# Controller-Modul.net
KiCad netlist of a schematic drawn in EAGLE
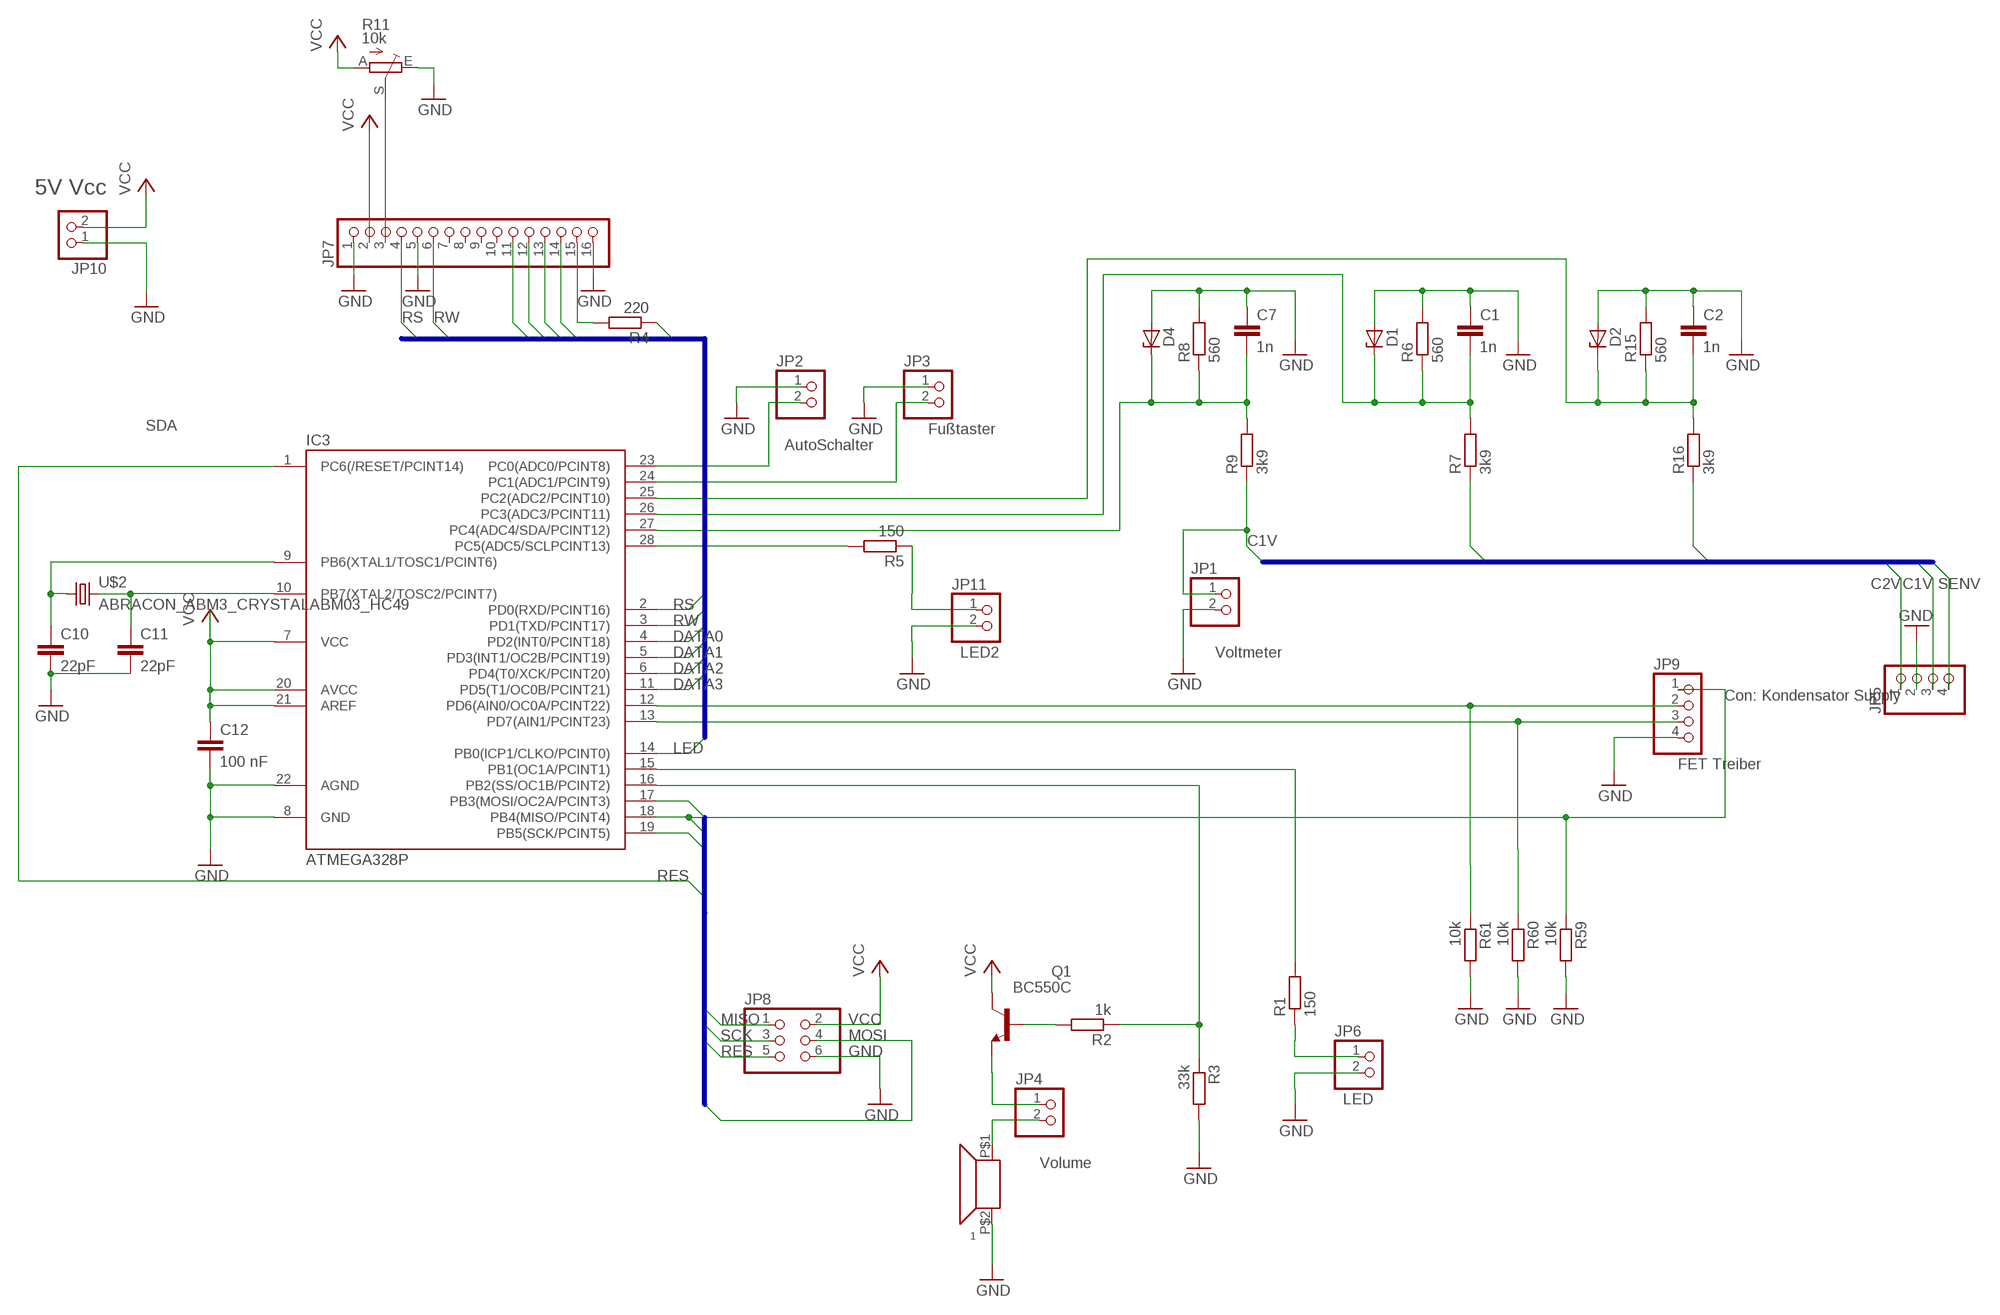
[diagram p0: schematic, sheet 1]

(export (version "E")
  (design (tool "Eeschema 10.0.6"))
  (components
    (comp (ref "1")
      (value "SUMMER4")
      (footprint "eagle-import:PIEZO-INDIKATOR-KPMG")
      (libsource (lib "eagle-import") (part "SUMMER4"))
    )
    (comp (ref "C1")
      (value "1n")
      (footprint "eagle-import:C0603K")
      (libsource (lib "eagle-import") (part "C-EUC0603K"))
    )
    (comp (ref "C2")
      (value "1n")
      (footprint "eagle-import:C0603K")
      (libsource (lib "eagle-import") (part "C-EUC0603K"))
    )
    (comp (ref "C7")
      (value "1n")
      (footprint "eagle-import:C0603K")
      (libsource (lib "eagle-import") (part "C-EUC0603K"))
    )
    (comp (ref "C10")
      (value "22pF")
      (footprint "eagle-import:C0603K")
      (libsource (lib "eagle-import") (part "resistor_C-EUC0603K"))
    )
    (comp (ref "C11")
      (value "22pF")
      (footprint "eagle-import:C0603K")
      (libsource (lib "eagle-import") (part "resistor_C-EUC0603K"))
    )
    (comp (ref "C12")
      (value "100 nF")
      (footprint "eagle-import:C0603")
      (libsource (lib "eagle-import") (part "resistor_C-EUC0603"))
    )
    (comp (ref "D1")
      (value "ZENER-DIODESOT23")
      (footprint "eagle-import:SOT23")
      (libsource (lib "eagle-import") (part "ZENER-DIODESOT23"))
    )
    (comp (ref "D2")
      (value "ZENER-DIODESOT23")
      (footprint "eagle-import:SOT23")
      (libsource (lib "eagle-import") (part "ZENER-DIODESOT23"))
    )
    (comp (ref "D4")
      (value "ZENER-DIODESOT23")
      (footprint "eagle-import:SOT23")
      (libsource (lib "eagle-import") (part "ZENER-DIODESOT23"))
    )
    (comp (ref "IC3")
      (value "ATMEGA328P")
      (footprint "eagle-import:DIL28-3")
      (libsource (lib "eagle-import") (part "MEGA48/88/168-PU"))
    )
    (comp (ref "JP1")
      (value "PINHD-1X2")
      (footprint "eagle-import:1X02")
      (libsource (lib "eagle-import") (part "PINHD-1X2"))
    )
    (comp (ref "JP2")
      (value "PINHD-1X2")
      (footprint "eagle-import:1X02")
      (libsource (lib "eagle-import") (part "PINHD-1X2"))
    )
    (comp (ref "JP3")
      (value "PINHD-1X2")
      (footprint "eagle-import:1X02")
      (libsource (lib "eagle-import") (part "PINHD-1X2"))
    )
    (comp (ref "JP4")
      (value "PINHD-1X2")
      (footprint "eagle-import:1X02")
      (libsource (lib "eagle-import") (part "PINHD-1X2"))
    )
    (comp (ref "JP5")
      (value "PINHD-1X4")
      (footprint "eagle-import:1X04")
      (libsource (lib "eagle-import") (part "PINHD-1X4"))
    )
    (comp (ref "JP6")
      (value "PINHD-1X2")
      (footprint "eagle-import:1X02")
      (libsource (lib "eagle-import") (part "PINHD-1X2"))
    )
    (comp (ref "JP7")
      (value "PINHD-1X16")
      (footprint "eagle-import:1X16")
      (libsource (lib "eagle-import") (part "PINHD-1X16"))
    )
    (comp (ref "JP8")
      (value "PINHD-2X3")
      (footprint "eagle-import:2X03")
      (libsource (lib "eagle-import") (part "PINHD-2X3"))
    )
    (comp (ref "JP9")
      (value "PINHD-1X4")
      (footprint "eagle-import:1X04")
      (libsource (lib "eagle-import") (part "PINHD-1X4"))
    )
    (comp (ref "JP10")
      (value "PINHD-1X2")
      (footprint "eagle-import:1X02")
      (libsource (lib "eagle-import") (part "PINHD-1X2"))
    )
    (comp (ref "JP11")
      (value "PINHD-1X2")
      (footprint "eagle-import:1X02")
      (libsource (lib "eagle-import") (part "PINHD-1X2"))
    )
    (comp (ref "Q1")
      (value "BC550C")
      (footprint "eagle-import:TO92-EBC")
      (libsource (lib "eagle-import") (part "BC550C"))
    )
    (comp (ref "R1")
      (value "150")
      (footprint "eagle-import:R1206")
      (libsource (lib "eagle-import") (part "R-EU_R1206"))
    )
    (comp (ref "R2")
      (value "1k")
      (footprint "eagle-import:R1206")
      (libsource (lib "eagle-import") (part "resistor_R-EU_R1206"))
    )
    (comp (ref "R3")
      (value "33k")
      (footprint "eagle-import:R1206")
      (libsource (lib "eagle-import") (part "resistor_R-EU_R1206"))
    )
    (comp (ref "R4")
      (value "220")
      (footprint "eagle-import:R1206")
      (libsource (lib "eagle-import") (part "resistor_R-EU_R1206"))
    )
    (comp (ref "R5")
      (value "150")
      (footprint "eagle-import:R1206")
      (libsource (lib "eagle-import") (part "R-EU_R1206"))
    )
    (comp (ref "R6")
      (value "560")
      (footprint "eagle-import:R1206")
      (libsource (lib "eagle-import") (part "resistor_R-EU_R1206"))
    )
    (comp (ref "R7")
      (value "3k9")
      (footprint "eagle-import:R1206")
      (libsource (lib "eagle-import") (part "resistor_R-EU_R1206"))
    )
    (comp (ref "R8")
      (value "560")
      (footprint "eagle-import:R1206")
      (libsource (lib "eagle-import") (part "resistor_R-EU_R1206"))
    )
    (comp (ref "R9")
      (value "3k9")
      (footprint "eagle-import:R1206")
      (libsource (lib "eagle-import") (part "resistor_R-EU_R1206"))
    )
    (comp (ref "R11")
      (value "10k")
      (footprint "eagle-import:PT-10")
      (libsource (lib "eagle-import") (part "TRIM_EU-PT10"))
    )
    (comp (ref "R15")
      (value "560")
      (footprint "eagle-import:R1206")
      (libsource (lib "eagle-import") (part "resistor_R-EU_R1206"))
    )
    (comp (ref "R16")
      (value "3k9")
      (footprint "eagle-import:R1206")
      (libsource (lib "eagle-import") (part "resistor_R-EU_R1206"))
    )
    (comp (ref "R59")
      (value "10k")
      (footprint "eagle-import:R1206")
      (libsource (lib "eagle-import") (part "resistor_R-EU_R1206"))
    )
    (comp (ref "R60")
      (value "10k")
      (footprint "eagle-import:R1206")
      (libsource (lib "eagle-import") (part "resistor_R-EU_R1206"))
    )
    (comp (ref "R61")
      (value "10k")
      (footprint "eagle-import:R1206")
      (libsource (lib "eagle-import") (part "resistor_R-EU_R1206"))
    )
    (comp (ref "U$2")
      (value "ABRACON_ABM3_CRYSTALABM03_HC49")
      (footprint "eagle-import:ABM03_HC49")
      (libsource (lib "eagle-import") (part "ABRACON_ABM3_CRYSTALABM03_HC49"))
    )
  )
  (nets
    (net (code "1") (name "/C1V") (class "Default")
      (node (ref "JP1") (pin "1") (pinfunction "1_1") (pintype "passive"))
      (node (ref "JP5") (pin "3") (pinfunction "3_3") (pintype "passive"))
      (node (ref "R9") (pin "1") (pinfunction "1_1") (pintype "passive"))
    )
    (net (code "2") (name "/C2V") (class "Default")
      (node (ref "JP5") (pin "1") (pinfunction "1_1") (pintype "passive"))
      (node (ref "R7") (pin "1") (pinfunction "1_1") (pintype "passive"))
    )
    (net (code "3") (name "/DATA0") (class "Default")
      (node (ref "IC3") (pin "4") (pinfunction "PD2(INT0/PCINT18)_4") (pintype "bidirectional"))
      (node (ref "JP7") (pin "11") (pinfunction "11_11") (pintype "passive"))
    )
    (net (code "4") (name "/DATA1") (class "Default")
      (node (ref "IC3") (pin "5") (pinfunction "PD3(INT1/OC2B/PCINT19)_5") (pintype "bidirectional"))
      (node (ref "JP7") (pin "12") (pinfunction "12_12") (pintype "passive"))
    )
    (net (code "5") (name "/DATA2") (class "Default")
      (node (ref "IC3") (pin "6") (pinfunction "PD4(T0/XCK/PCINT20)_6") (pintype "bidirectional"))
      (node (ref "JP7") (pin "13") (pinfunction "13_13") (pintype "passive"))
    )
    (net (code "6") (name "/DATA3") (class "Default")
      (node (ref "IC3") (pin "11") (pinfunction "PD5(T1/OC0B/PCINT21)_11") (pintype "bidirectional"))
      (node (ref "JP7") (pin "14") (pinfunction "14_14") (pintype "passive"))
    )
    (net (code "7") (name "/LED") (class "Default")
      (node (ref "IC3") (pin "14") (pinfunction "PB0(ICP1/CLKO/PCINT0)_14") (pintype "bidirectional"))
      (node (ref "R4") (pin "1") (pinfunction "1_1") (pintype "passive"))
    )
    (net (code "8") (name "/MISO") (class "Default")
      (node (ref "IC3") (pin "18") (pinfunction "PB4(MISO/PCINT4)_18") (pintype "bidirectional"))
      (node (ref "JP8") (pin "1") (pinfunction "1_1") (pintype "passive"))
      (node (ref "JP9") (pin "1") (pinfunction "1_1") (pintype "passive"))
      (node (ref "R59") (pin "1") (pinfunction "1_1") (pintype "passive"))
    )
    (net (code "9") (name "/MOSI") (class "Default")
      (node (ref "IC3") (pin "17") (pinfunction "PB3(MOSI/OC2A/PCINT3)_17") (pintype "bidirectional"))
      (node (ref "JP8") (pin "4") (pinfunction "4_4") (pintype "passive"))
    )
    (net (code "10") (name "/RES") (class "Default")
      (node (ref "IC3") (pin "1") (pinfunction "PC6(/RESET/PCINT14)_1") (pintype "bidirectional"))
      (node (ref "JP8") (pin "5") (pinfunction "5_5") (pintype "passive"))
    )
    (net (code "11") (name "/RS") (class "Default")
      (node (ref "IC3") (pin "2") (pinfunction "PD0(RXD/PCINT16)_2") (pintype "bidirectional"))
      (node (ref "JP7") (pin "4") (pinfunction "4_4") (pintype "passive"))
    )
    (net (code "12") (name "/RW") (class "Default")
      (node (ref "IC3") (pin "3") (pinfunction "PD1(TXD/PCINT17)_3") (pintype "bidirectional"))
      (node (ref "JP7") (pin "6") (pinfunction "6_6") (pintype "passive"))
    )
    (net (code "13") (name "/SCK") (class "Default")
      (node (ref "IC3") (pin "19") (pinfunction "PB5(SCK/PCINT5)_19") (pintype "bidirectional"))
      (node (ref "JP8") (pin "3") (pinfunction "3_3") (pintype "passive"))
    )
    (net (code "14") (name "/SENV") (class "Default")
      (node (ref "JP5") (pin "4") (pinfunction "4_4") (pintype "passive"))
      (node (ref "R16") (pin "1") (pinfunction "1_1") (pintype "passive"))
    )
    (net (code "15") (name "GND") (class "Default")
      (node (ref "1") (pin "P$2") (pinfunction "+_P$2") (pintype "passive"))
      (node (ref "C1") (pin "1") (pinfunction "1_1") (pintype "passive"))
      (node (ref "C10") (pin "2") (pinfunction "2_2") (pintype "passive"))
      (node (ref "C11") (pin "2") (pinfunction "2_2") (pintype "passive"))
      (node (ref "C12") (pin "2") (pinfunction "2_2") (pintype "passive"))
      (node (ref "C2") (pin "1") (pinfunction "1_1") (pintype "passive"))
      (node (ref "C7") (pin "1") (pinfunction "1_1") (pintype "passive"))
      (node (ref "D1") (pin "1") (pinfunction "A_1") (pintype "passive"))
      (node (ref "D2") (pin "1") (pinfunction "A_1") (pintype "passive"))
      (node (ref "D4") (pin "1") (pinfunction "A_1") (pintype "passive"))
      (node (ref "IC3") (pin "22") (pinfunction "AGND_22") (pintype "power_in"))
      (node (ref "IC3") (pin "8") (pinfunction "GND_8") (pintype "power_in"))
      (node (ref "JP1") (pin "2") (pinfunction "2_2") (pintype "passive"))
      (node (ref "JP10") (pin "1") (pinfunction "1_1") (pintype "passive"))
      (node (ref "JP11") (pin "2") (pinfunction "2_2") (pintype "passive"))
      (node (ref "JP2") (pin "1") (pinfunction "1_1") (pintype "passive"))
      (node (ref "JP3") (pin "1") (pinfunction "1_1") (pintype "passive"))
      (node (ref "JP5") (pin "2") (pinfunction "2_2") (pintype "passive"))
      (node (ref "JP6") (pin "2") (pinfunction "2_2") (pintype "passive"))
      (node (ref "JP7") (pin "1") (pinfunction "1_1") (pintype "passive"))
      (node (ref "JP7") (pin "16") (pinfunction "16_16") (pintype "passive"))
      (node (ref "JP7") (pin "5") (pinfunction "5_5") (pintype "passive"))
      (node (ref "JP8") (pin "6") (pinfunction "6_6") (pintype "passive"))
      (node (ref "JP9") (pin "4") (pinfunction "4_4") (pintype "passive"))
      (node (ref "R11") (pin "E") (pinfunction "E_E") (pintype "passive"))
      (node (ref "R15") (pin "2") (pinfunction "2_2") (pintype "passive"))
      (node (ref "R3") (pin "2") (pinfunction "2_2") (pintype "passive"))
      (node (ref "R59") (pin "2") (pinfunction "2_2") (pintype "passive"))
      (node (ref "R6") (pin "2") (pinfunction "2_2") (pintype "passive"))
      (node (ref "R60") (pin "2") (pinfunction "2_2") (pintype "passive"))
      (node (ref "R61") (pin "2") (pinfunction "2_2") (pintype "passive"))
      (node (ref "R8") (pin "2") (pinfunction "2_2") (pintype "passive"))
    )
    (net (code "16") (name "Net-(1--)") (class "Default")
      (node (ref "1") (pin "P$1") (pinfunction "-_P$1") (pintype "passive"))
      (node (ref "JP4") (pin "2") (pinfunction "2_2") (pintype "passive"))
    )
    (net (code "17") (name "Net-(D1-C)") (class "Default")
      (node (ref "C1") (pin "2") (pinfunction "2_2") (pintype "passive"))
      (node (ref "D1") (pin "3") (pinfunction "C_3") (pintype "passive"))
      (node (ref "IC3") (pin "26") (pinfunction "PC3(ADC3/PCINT11)_26") (pintype "bidirectional"))
      (node (ref "R6") (pin "1") (pinfunction "1_1") (pintype "passive"))
      (node (ref "R7") (pin "2") (pinfunction "2_2") (pintype "passive"))
    )
    (net (code "18") (name "Net-(D2-C)") (class "Default")
      (node (ref "C2") (pin "2") (pinfunction "2_2") (pintype "passive"))
      (node (ref "D2") (pin "3") (pinfunction "C_3") (pintype "passive"))
      (node (ref "IC3") (pin "25") (pinfunction "PC2(ADC2/PCINT10)_25") (pintype "bidirectional"))
      (node (ref "R15") (pin "1") (pinfunction "1_1") (pintype "passive"))
      (node (ref "R16") (pin "2") (pinfunction "2_2") (pintype "passive"))
    )
    (net (code "19") (name "Net-(D4-C)") (class "Default")
      (node (ref "C7") (pin "2") (pinfunction "2_2") (pintype "passive"))
      (node (ref "D4") (pin "3") (pinfunction "C_3") (pintype "passive"))
      (node (ref "IC3") (pin "27") (pinfunction "PC4(ADC4/SDA/PCINT12)_27") (pintype "bidirectional"))
      (node (ref "R8") (pin "1") (pinfunction "1_1") (pintype "passive"))
      (node (ref "R9") (pin "2") (pinfunction "2_2") (pintype "passive"))
    )
    (net (code "20") (name "Net-(IC3-PB1(OC1A{slash}PCINT1))") (class "Default")
      (node (ref "IC3") (pin "15") (pinfunction "PB1(OC1A/PCINT1)_15") (pintype "bidirectional"))
      (node (ref "R1") (pin "2") (pinfunction "2_2") (pintype "passive"))
    )
    (net (code "21") (name "Net-(IC3-PB2(SS{slash}OC1B{slash}PCINT2))") (class "Default")
      (node (ref "IC3") (pin "16") (pinfunction "PB2(SS/OC1B/PCINT2)_16") (pintype "bidirectional"))
      (node (ref "R2") (pin "1") (pinfunction "1_1") (pintype "passive"))
      (node (ref "R3") (pin "1") (pinfunction "1_1") (pintype "passive"))
    )
    (net (code "22") (name "Net-(IC3-PB6(XTAL1{slash}TOSC1{slash}PCINT6))") (class "Default")
      (node (ref "C10") (pin "1") (pinfunction "1_1") (pintype "passive"))
      (node (ref "IC3") (pin "9") (pinfunction "PB6(XTAL1/TOSC1/PCINT6)_9") (pintype "bidirectional"))
      (node (ref "U$2") (pin "1") (pinfunction "1_1") (pintype "passive"))
    )
    (net (code "23") (name "Net-(IC3-PB7(XTAL2{slash}TOSC2{slash}PCINT7))") (class "Default")
      (node (ref "C11") (pin "1") (pinfunction "1_1") (pintype "passive"))
      (node (ref "IC3") (pin "10") (pinfunction "PB7(XTAL2/TOSC2/PCINT7)_10") (pintype "bidirectional"))
      (node (ref "U$2") (pin "2") (pinfunction "2_2") (pintype "passive"))
    )
    (net (code "24") (name "Net-(IC3-PC0(ADC0{slash}PCINT8))") (class "Default")
      (node (ref "IC3") (pin "23") (pinfunction "PC0(ADC0/PCINT8)_23") (pintype "bidirectional"))
      (node (ref "JP2") (pin "2") (pinfunction "2_2") (pintype "passive"))
    )
    (net (code "25") (name "Net-(IC3-PC1(ADC1{slash}PCINT9))") (class "Default")
      (node (ref "IC3") (pin "24") (pinfunction "PC1(ADC1/PCINT9)_24") (pintype "bidirectional"))
      (node (ref "JP3") (pin "2") (pinfunction "2_2") (pintype "passive"))
    )
    (net (code "26") (name "Net-(IC3-PC5(ADC5{slash}SCLPCINT13))") (class "Default")
      (node (ref "IC3") (pin "28") (pinfunction "PC5(ADC5/SCLPCINT13)_28") (pintype "bidirectional"))
      (node (ref "R5") (pin "2") (pinfunction "2_2") (pintype "passive"))
    )
    (net (code "27") (name "Net-(IC3-PD6(AIN0{slash}OC0A{slash}PCINT22))") (class "Default")
      (node (ref "IC3") (pin "12") (pinfunction "PD6(AIN0/OC0A/PCINT22)_12") (pintype "bidirectional"))
      (node (ref "JP9") (pin "2") (pinfunction "2_2") (pintype "passive"))
      (node (ref "R61") (pin "1") (pinfunction "1_1") (pintype "passive"))
    )
    (net (code "28") (name "Net-(IC3-PD7(AIN1{slash}PCINT23))") (class "Default")
      (node (ref "IC3") (pin "13") (pinfunction "PD7(AIN1/PCINT23)_13") (pintype "bidirectional"))
      (node (ref "JP9") (pin "3") (pinfunction "3_3") (pintype "passive"))
      (node (ref "R60") (pin "1") (pinfunction "1_1") (pintype "passive"))
    )
    (net (code "29") (name "Net-(JP4-Pad1)") (class "Default")
      (node (ref "JP4") (pin "1") (pinfunction "1_1") (pintype "passive"))
      (node (ref "Q1") (pin "E") (pinfunction "E_E") (pintype "passive"))
    )
    (net (code "30") (name "Net-(JP6-Pad1)") (class "Default")
      (node (ref "JP6") (pin "1") (pinfunction "1_1") (pintype "passive"))
      (node (ref "R1") (pin "1") (pinfunction "1_1") (pintype "passive"))
    )
    (net (code "31") (name "Net-(JP7-Pad3)") (class "Default")
      (node (ref "JP7") (pin "3") (pinfunction "3_3") (pintype "passive"))
      (node (ref "R11") (pin "S") (pinfunction "S_S") (pintype "passive"))
    )
    (net (code "32") (name "Net-(JP7-Pad15)") (class "Default")
      (node (ref "JP7") (pin "15") (pinfunction "15_15") (pintype "passive"))
      (node (ref "R4") (pin "2") (pinfunction "2_2") (pintype "passive"))
    )
    (net (code "33") (name "Net-(JP11-Pad1)") (class "Default")
      (node (ref "JP11") (pin "1") (pinfunction "1_1") (pintype "passive"))
      (node (ref "R5") (pin "1") (pinfunction "1_1") (pintype "passive"))
    )
    (net (code "34") (name "Net-(Q1-PadB)") (class "Default")
      (node (ref "Q1") (pin "B") (pinfunction "B_B") (pintype "passive"))
      (node (ref "R2") (pin "2") (pinfunction "2_2") (pintype "passive"))
    )
    (net (code "35") (name "VCC") (class "Default")
      (node (ref "C12") (pin "1") (pinfunction "1_1") (pintype "passive"))
      (node (ref "IC3") (pin "20") (pinfunction "AVCC_20") (pintype "passive"))
      (node (ref "IC3") (pin "21") (pinfunction "AREF_21") (pintype "passive"))
      (node (ref "IC3") (pin "7") (pinfunction "VCC_7") (pintype "power_in"))
      (node (ref "JP10") (pin "2") (pinfunction "2_2") (pintype "passive"))
      (node (ref "JP7") (pin "2") (pinfunction "2_2") (pintype "passive"))
      (node (ref "JP8") (pin "2") (pinfunction "2_2") (pintype "passive"))
      (node (ref "Q1") (pin "C") (pinfunction "C_C") (pintype "passive"))
      (node (ref "R11") (pin "A") (pinfunction "A_A") (pintype "passive"))
    )
    (net (code "36") (name "unconnected-(JP7-Pad7)") (class "Default")
      (node (ref "JP7") (pin "7") (pinfunction "7_7") (pintype "passive"))
    )
    (net (code "37") (name "unconnected-(JP7-Pad8)") (class "Default")
      (node (ref "JP7") (pin "8") (pinfunction "8_8") (pintype "passive"))
    )
    (net (code "38") (name "unconnected-(JP7-Pad9)") (class "Default")
      (node (ref "JP7") (pin "9") (pinfunction "9_9") (pintype "passive"))
    )
    (net (code "39") (name "unconnected-(JP7-Pad10)") (class "Default")
      (node (ref "JP7") (pin "10") (pinfunction "10_10") (pintype "passive"))
    )
  )
)
